# USER_IO.net
KiCad netlist of a schematic drawn in Altium Designer
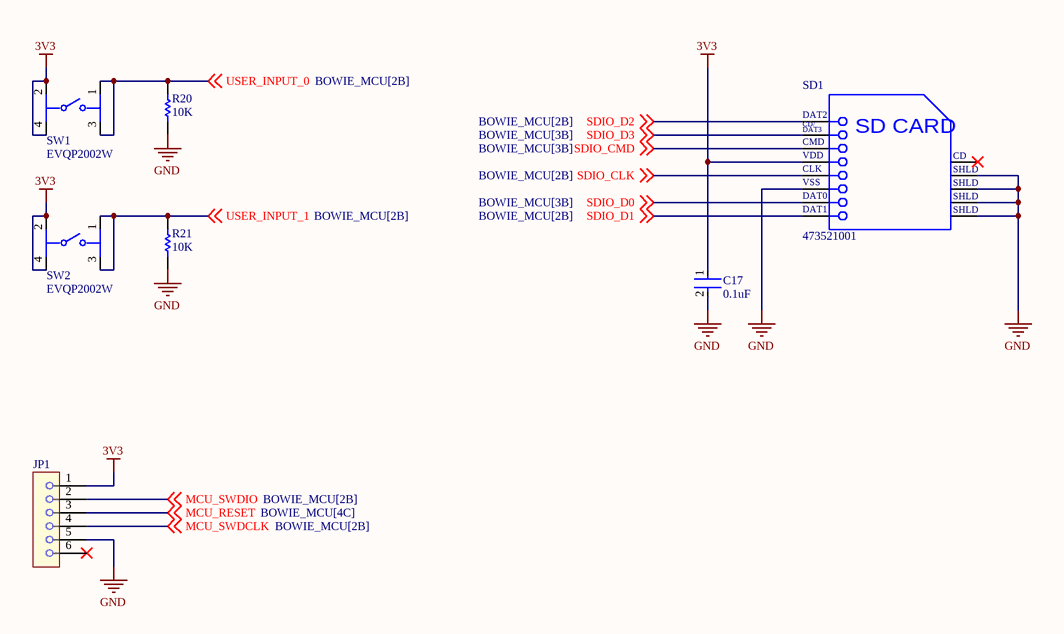
[diagram p0: USER_IO.SchDoc]

(export (version "E")
  (design (tool "Eeschema 10.0.6"))
  (components
    (comp (ref "C17")
      (value "0.1uF")
      (footprint "FP-GRM15-MFG")
      (description "CAP CER 0.1UF 16V X7R 0402")
      (fields (field (name "MANUFACTURER PART NUMBER") "GRM155R71C104KA88D") (field (name "TOLERANCE") "10%"))
      (libsource (lib "Altium Content Vault") (part "236180d848d6139a670b325ea6854c9"))
    )
    (comp (ref "JP1")
      (value "TC2030-6-NL-FOOTPRINT")
      (footprint "TAG_TC2030_NL_6")
      (description "CONN, FP, 2X3, .05, DEBUG, SMT")
      (fields (field (name "MANUFACTURER") "NO PART") (field (name "PART NUMBER") "FOOTPRINT ONLY"))
      (libsource (lib "Phalanx") (part "TC2030-6-NL-FOOTPRINT"))
    )
    (comp (ref "R20")
      (value "10K")
      (footprint "RESC1005X40X25ML05T10")
      (fields (field (name "PART NUMBER") "CRCW040210K0FKEDHP") (field (name "MANUFACTURER") "Vishay Dale"))
      (libsource (lib "Altium Content Vault") (part "RES"))
    )
    (comp (ref "R21")
      (value "10K")
      (footprint "RESC1005X40X25ML05T10")
      (fields (field (name "PART NUMBER") "CRCW040210K0FKEDHP") (field (name "MANUFACTURER") "Vishay Dale"))
      (libsource (lib "Altium Content Vault") (part "RES"))
    )
    (comp (ref "SD1")
      (value "473521001")
      (footprint "MOLX-473521001_V")
      (description "MicroSD(TM), Pitch 1.1 mm, 8 Position, Height 1.88 mm, -20 to 85 degC, RoHS, Tape and Reel")
      (fields (field (name "MANUFACTURER") "Molex"))
      (libsource (lib "Altium Content Vault") (part "CN-SD-8-1SW-4S"))
    )
    (comp (ref "SW1")
      (value "EVQP2002W")
      (footprint "FP-EVQP2002W-MFG")
      (description "SWITCH TACTILE SPST-NO 0.02A 15V")
      (libsource (lib "Altium Content Vault") (part "3d0627a2b91f68de89d2c38e02ec842"))
    )
    (comp (ref "SW2")
      (value "EVQP2002W")
      (footprint "FP-EVQP2002W-MFG")
      (description "SWITCH TACTILE SPST-NO 0.02A 15V")
      (libsource (lib "Altium Content Vault") (part "3d0627a2b91f68de89d2c38e02ec842"))
    )
  )
  (nets
    (net (code "1") (name "3V3") (class "Default")
      (node (ref "C17") (pin "1") (pinfunction "1_1") (pintype "passive"))
      (node (ref "JP1") (pin "1") (pinfunction "1_1") (pintype "passive"))
      (node (ref "SD1") (pin "4") (pinfunction "VDD_4") (pintype "passive"))
      (node (ref "SW1") (pin "2") (pinfunction "2_2") (pintype "passive"))
      (node (ref "SW1") (pin "4") (pinfunction "4_4") (pintype "passive"))
      (node (ref "SW2") (pin "2") (pinfunction "2_2") (pintype "passive"))
      (node (ref "SW2") (pin "4") (pinfunction "4_4") (pintype "passive"))
    )
    (net (code "2") (name "GND") (class "Default")
      (node (ref "C17") (pin "2") (pinfunction "2_2") (pintype "passive"))
      (node (ref "JP1") (pin "5") (pinfunction "5_5") (pintype "passive"))
      (node (ref "R20") (pin "1") (pinfunction "1_1") (pintype "passive"))
      (node (ref "R21") (pin "1") (pinfunction "1_1") (pintype "passive"))
      (node (ref "SD1") (pin "10") (pinfunction "SHLD_10") (pintype "passive"))
      (node (ref "SD1") (pin "11") (pinfunction "SHLD_11") (pintype "passive"))
      (node (ref "SD1") (pin "12") (pinfunction "SHLD_12") (pintype "passive"))
      (node (ref "SD1") (pin "13") (pinfunction "SHLD_13") (pintype "passive"))
      (node (ref "SD1") (pin "6") (pinfunction "VSS_6") (pintype "passive"))
    )
    (net (code "3") (name "MCU_RESET") (class "Default")
      (node (ref "JP1") (pin "3") (pinfunction "3_3") (pintype "passive"))
    )
    (net (code "4") (name "MCU_SWDCLK") (class "Default")
      (node (ref "JP1") (pin "4") (pinfunction "4_4") (pintype "passive"))
    )
    (net (code "5") (name "MCU_SWDIO") (class "Default")
      (node (ref "JP1") (pin "2") (pinfunction "2_2") (pintype "passive"))
    )
    (net (code "6") (name "SDIO_CLK") (class "Default")
      (node (ref "SD1") (pin "5") (pinfunction "CLK_5") (pintype "passive"))
    )
    (net (code "7") (name "SDIO_CMD") (class "Default")
      (node (ref "SD1") (pin "3") (pinfunction "CMD_3") (pintype "passive"))
    )
    (net (code "8") (name "SDIO_D0") (class "Default")
      (node (ref "SD1") (pin "7") (pinfunction "DAT0_7") (pintype "passive"))
    )
    (net (code "9") (name "SDIO_D1") (class "Default")
      (node (ref "SD1") (pin "8") (pinfunction "DAT1_8") (pintype "passive"))
    )
    (net (code "10") (name "SDIO_D2") (class "Default")
      (node (ref "SD1") (pin "1") (pinfunction "DAT2_1") (pintype "passive"))
    )
    (net (code "11") (name "SDIO_D3") (class "Default")
      (node (ref "SD1") (pin "2") (pinfunction "CD/DAT3_2") (pintype "passive"))
    )
    (net (code "12") (name "USER_INPUT_0") (class "Default")
      (node (ref "R20") (pin "2") (pinfunction "2_2") (pintype "passive"))
      (node (ref "SW1") (pin "1") (pinfunction "1_1") (pintype "passive"))
      (node (ref "SW1") (pin "3") (pinfunction "3_3") (pintype "passive"))
    )
    (net (code "13") (name "USER_INPUT_1") (class "Default")
      (node (ref "R21") (pin "2") (pinfunction "2_2") (pintype "passive"))
      (node (ref "SW2") (pin "1") (pinfunction "1_1") (pintype "passive"))
      (node (ref "SW2") (pin "3") (pinfunction "3_3") (pintype "passive"))
    )
    (net (code "14") (name "unconnected-(JP1-Pad6)") (class "Default")
      (node (ref "JP1") (pin "6") (pinfunction "6_6") (pintype "passive+no_connect"))
    )
    (net (code "15") (name "unconnected-(SD1-CD-Pad9)") (class "Default")
      (node (ref "SD1") (pin "9") (pinfunction "CD_9") (pintype "passive+no_connect"))
    )
  )
)
